# untitled.net
KiCad netlist of a schematic drawn in EAGLE
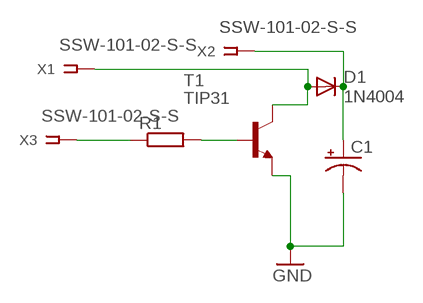
[diagram p0: schematic, sheet 1]

(export (version "E")
  (design (tool "Eeschema 10.0.6"))
  (components
    (comp (ref "C1")
      (value "CPOL-USE5-5")
      (footprint "eagle-import:E5-5")
      (libsource (lib "eagle-import") (part "CPOL-USE5-5"))
    )
    (comp (ref "D1")
      (value "1N4004")
      (footprint "eagle-import:DO41-10")
      (libsource (lib "eagle-import") (part "1N4004"))
    )
    (comp (ref "R1")
      (value "R-EU_0207/10")
      (footprint "eagle-import:0207_10")
      (libsource (lib "eagle-import") (part "R-EU_0207/10"))
    )
    (comp (ref "T1")
      (value "TIP31")
      (footprint "eagle-import:TO220")
      (libsource (lib "eagle-import") (part "TIP31"))
    )
    (comp (ref "X1")
      (value "SSW-101-02-S-S")
      (footprint "eagle-import:SSW-101-02-S-S")
      (libsource (lib "eagle-import") (part "SSW-101-02-S-S"))
    )
    (comp (ref "X2")
      (value "SSW-101-02-S-S")
      (footprint "eagle-import:SSW-101-02-S-S")
      (libsource (lib "eagle-import") (part "SSW-101-02-S-S"))
    )
    (comp (ref "X3")
      (value "SSW-101-02-S-S")
      (footprint "eagle-import:SSW-101-02-S-S")
      (libsource (lib "eagle-import") (part "SSW-101-02-S-S"))
    )
  )
  (nets
    (net (code "1") (name "GND") (class "Default")
      (node (ref "C1") (pin "-") (pinfunction "-_-") (pintype "passive"))
      (node (ref "T1") (pin "3") (pinfunction "E_3") (pintype "passive"))
    )
    (net (code "2") (name "Net-(C1-Pad+)") (class "Default")
      (node (ref "C1") (pin "+") (pinfunction "+_+") (pintype "passive"))
      (node (ref "D1") (pin "C") (pinfunction "C_C") (pintype "passive"))
      (node (ref "X2") (pin "1") (pinfunction "1_1") (pintype "passive"))
    )
    (net (code "3") (name "Net-(R1-Pad1)") (class "Default")
      (node (ref "R1") (pin "1") (pinfunction "1_1") (pintype "passive"))
      (node (ref "X3") (pin "1") (pinfunction "1_1") (pintype "passive"))
    )
    (net (code "4") (name "Net-(T1-B)") (class "Default")
      (node (ref "R1") (pin "2") (pinfunction "2_2") (pintype "passive"))
      (node (ref "T1") (pin "1") (pinfunction "B_1") (pintype "passive"))
    )
    (net (code "5") (name "Net-(T1-C)") (class "Default")
      (node (ref "D1") (pin "A") (pinfunction "A_A") (pintype "passive"))
      (node (ref "T1") (pin "2") (pinfunction "C_2") (pintype "passive"))
      (node (ref "X1") (pin "1") (pinfunction "1_1") (pintype "passive"))
    )
  )
)
